# sa612_lm386.net
KiCad netlist of a schematic drawn in EAGLE
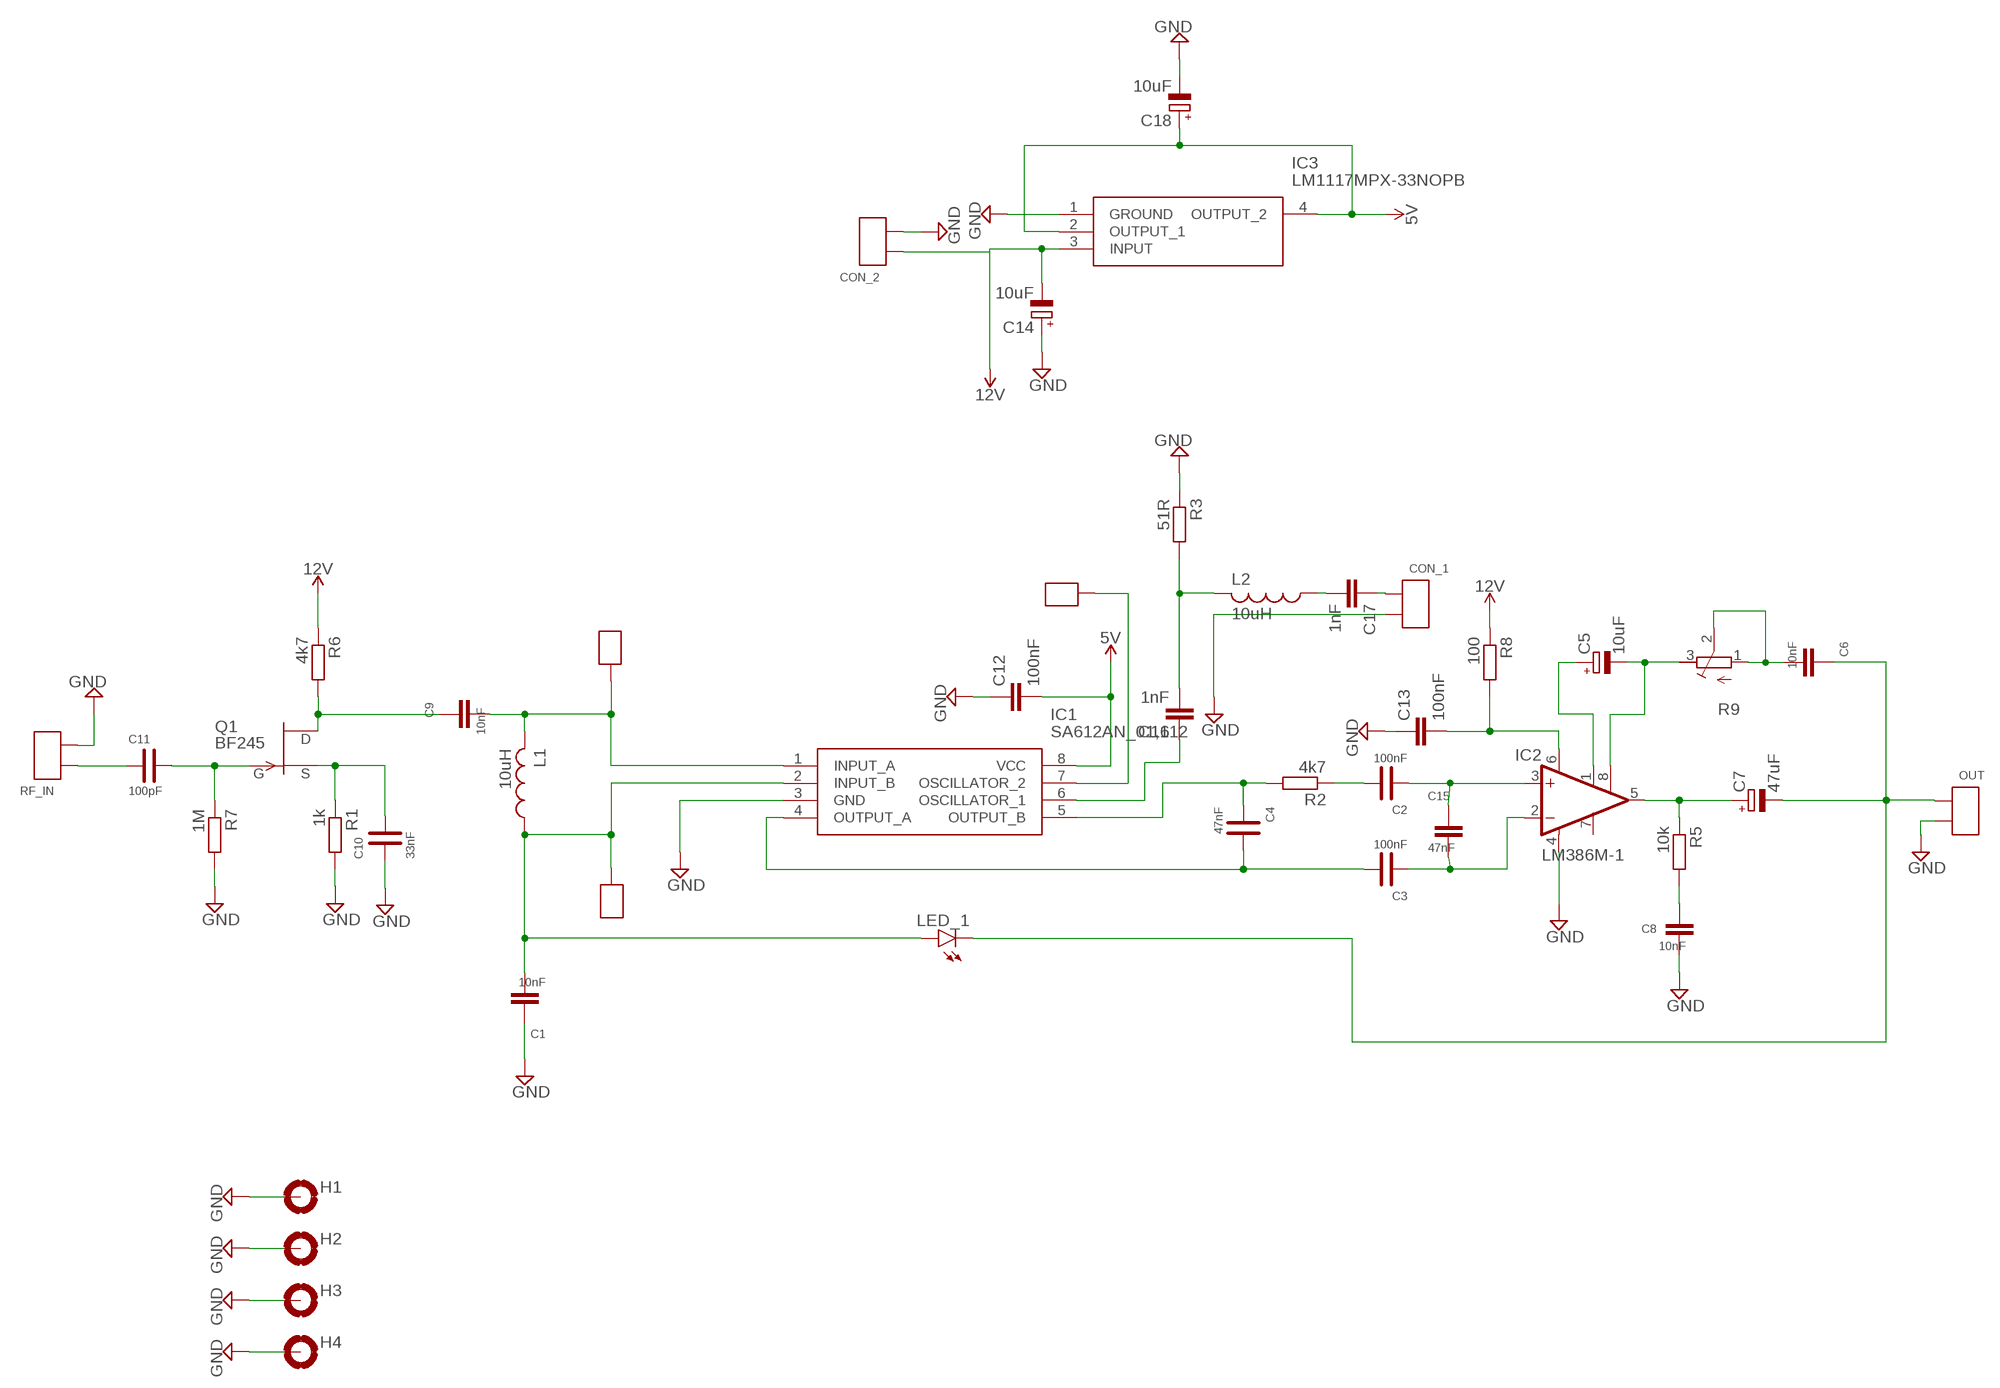
[diagram p0: schematic, sheet 1]

(export (version "E")
  (design (tool "Eeschema 10.0.6"))
  (components
    (comp (ref "C1")
      (value "10nF")
      (footprint "eagle-import:C0805")
      (libsource (lib "eagle-import") (part "C_0805_SMD"))
    )
    (comp (ref "C2")
      (value "100nF")
      (footprint "eagle-import:C0805K")
      (libsource (lib "eagle-import") (part "C_0805_PTH"))
    )
    (comp (ref "C3")
      (value "100nF")
      (footprint "eagle-import:C0805K")
      (libsource (lib "eagle-import") (part "C_0805_PTH"))
    )
    (comp (ref "C4")
      (value "47nF")
      (footprint "eagle-import:C0805K")
      (libsource (lib "eagle-import") (part "C_0805_PTH"))
    )
    (comp (ref "C5")
      (value "10uF")
      (footprint "eagle-import:E5-5")
      (libsource (lib "eagle-import") (part "C_POL"))
    )
    (comp (ref "C6")
      (value "10nF")
      (footprint "eagle-import:C0805")
      (libsource (lib "eagle-import") (part "C_0805_SMD"))
    )
    (comp (ref "C7")
      (value "47uF")
      (footprint "eagle-import:E5-5")
      (libsource (lib "eagle-import") (part "C_POL"))
    )
    (comp (ref "C8")
      (value "10nF")
      (footprint "eagle-import:C0805")
      (libsource (lib "eagle-import") (part "C_0805_SMD"))
    )
    (comp (ref "C9")
      (value "10nF")
      (footprint "eagle-import:C0805")
      (libsource (lib "eagle-import") (part "C_0805_SMD"))
    )
    (comp (ref "C10")
      (value "33nF")
      (footprint "eagle-import:C0805K")
      (libsource (lib "eagle-import") (part "C_0805_PTH"))
    )
    (comp (ref "C11")
      (value "100pF")
      (footprint "eagle-import:C0805K")
      (libsource (lib "eagle-import") (part "C_0805_PTH"))
    )
    (comp (ref "C12")
      (value "100nF")
      (footprint "eagle-import:C0805")
      (libsource (lib "eagle-import") (part "C_0805_SMD"))
    )
    (comp (ref "C13")
      (value "100nF")
      (footprint "eagle-import:C0805")
      (libsource (lib "eagle-import") (part "C_0805_SMD"))
    )
    (comp (ref "C14")
      (value "10uF")
      (footprint "eagle-import:E5-5")
      (libsource (lib "eagle-import") (part "C_POL"))
    )
    (comp (ref "C15")
      (value "47nF")
      (footprint "eagle-import:C0805")
      (libsource (lib "eagle-import") (part "C_0805_SMD"))
    )
    (comp (ref "C16")
      (value "1nF")
      (footprint "eagle-import:C0805")
      (libsource (lib "eagle-import") (part "C_0805_SMD"))
    )
    (comp (ref "C17")
      (value "1nF")
      (footprint "eagle-import:C0805")
      (libsource (lib "eagle-import") (part "C_0805_SMD"))
    )
    (comp (ref "C18")
      (value "10uF")
      (footprint "eagle-import:E5-5")
      (libsource (lib "eagle-import") (part "C_POL"))
    )
    (comp (ref "CON_1")
      (value "2X_SMD_PTH_PIN")
      (footprint "eagle-import:2X_SMD_PTH")
      (libsource (lib "eagle-import") (part "2X_SMD_PTH_PIN"))
    )
    (comp (ref "CON_2")
      (value "2X_SMD_PTH_PIN")
      (footprint "eagle-import:2X_SMD_PTH")
      (libsource (lib "eagle-import") (part "2X_SMD_PTH_PIN"))
    )
    (comp (ref "H1")
      (value "MOUNT-PAD-ROUND3.0")
      (footprint "eagle-import:3,0-PAD")
      (libsource (lib "eagle-import") (part "MOUNT-PAD-ROUND3.0"))
    )
    (comp (ref "H2")
      (value "MOUNT-PAD-ROUND3.0")
      (footprint "eagle-import:3,0-PAD")
      (libsource (lib "eagle-import") (part "MOUNT-PAD-ROUND3.0"))
    )
    (comp (ref "H3")
      (value "MOUNT-PAD-ROUND3.0")
      (footprint "eagle-import:3,0-PAD")
      (libsource (lib "eagle-import") (part "MOUNT-PAD-ROUND3.0"))
    )
    (comp (ref "H4")
      (value "MOUNT-PAD-ROUND3.0")
      (footprint "eagle-import:3,0-PAD")
      (libsource (lib "eagle-import") (part "MOUNT-PAD-ROUND3.0"))
    )
    (comp (ref "IC1")
      (value "SA612AN_01,112")
      (footprint "eagle-import:DIP762W53P254L950H420Q8N")
      (fields
        (field (name "MANUFACTURER_PART_NUMBER") "SA612AN/01,112")
        (field (name "MOUSER_PART_NUMBER") "771-SA612AN/01")
      )
      (libsource (lib "eagle-import") (part "SA612AN_01,112"))
    )
    (comp (ref "IC2")
      (value "LM386M-1")
      (footprint "eagle-import:SO08")
      (libsource (lib "eagle-import") (part "LM386?-M1"))
    )
    (comp (ref "IC3")
      (value "LM1117MPX-33NOPB")
      (footprint "eagle-import:SOT230P700X180-4N")
      (fields (field (name "MOUSER_PART_NUMBER") "863-LM1117MPX-33NOPB"))
      (libsource (lib "eagle-import") (part "LM1117MPX-33NOPB"))
    )
    (comp (ref "IN_A")
      (value "SMD_PIN")
      (footprint "eagle-import:SMD_PIN")
      (libsource (lib "eagle-import") (part "SMD_PIN"))
    )
    (comp (ref "IN_B")
      (value "SMD_PIN")
      (footprint "eagle-import:SMD_PIN")
      (libsource (lib "eagle-import") (part "SMD_PIN"))
    )
    (comp (ref "L1")
      (value "10uH")
      (footprint "eagle-import:M0805")
      (libsource (lib "eagle-import") (part "L_0805_PTH"))
    )
    (comp (ref "L2")
      (value "10uH")
      (footprint "eagle-import:M0805")
      (libsource (lib "eagle-import") (part "L_0805_PTH"))
    )
    (comp (ref "LED_1")
      (value "LED_0805_PTH")
      (footprint "eagle-import:CHIP-LED0805")
      (libsource (lib "eagle-import") (part "LED_0805_PTH"))
    )
    (comp (ref "OUT")
      (value "2X_SMD_PTH_PIN")
      (footprint "eagle-import:2X_SMD_PTH")
      (libsource (lib "eagle-import") (part "2X_SMD_PTH_PIN"))
    )
    (comp (ref "P_1")
      (value "SMD_PIN")
      (footprint "eagle-import:SMD_PIN")
      (libsource (lib "eagle-import") (part "SMD_PIN"))
    )
    (comp (ref "Q1")
      (value "BF245")
      (footprint "eagle-import:TO92")
      (libsource (lib "eagle-import") (part "BF245"))
    )
    (comp (ref "R1")
      (value "1k")
      (footprint "eagle-import:R0805")
      (libsource (lib "eagle-import") (part "R_0805_PTH"))
    )
    (comp (ref "R2")
      (value "4k7")
      (footprint "eagle-import:R0805W")
      (libsource (lib "eagle-import") (part "R_0805_SMD"))
    )
    (comp (ref "R3")
      (value "51R")
      (footprint "eagle-import:R0805W")
      (libsource (lib "eagle-import") (part "R_0805_SMD"))
    )
    (comp (ref "R5")
      (value "10k")
      (footprint "eagle-import:R0805W")
      (libsource (lib "eagle-import") (part "R_0805_SMD"))
    )
    (comp (ref "R6")
      (value "4k7")
      (footprint "eagle-import:R0805")
      (libsource (lib "eagle-import") (part "R_0805_PTH"))
    )
    (comp (ref "R7")
      (value "1M")
      (footprint "eagle-import:R0805")
      (libsource (lib "eagle-import") (part "R_0805_PTH"))
    )
    (comp (ref "R8")
      (value "100")
      (footprint "eagle-import:R0805W")
      (libsource (lib "eagle-import") (part "R_0805_SMD"))
    )
    (comp (ref "R9")
      (value "R-TRIMM64W")
      (footprint "eagle-import:RTRIM64W")
      (libsource (lib "eagle-import") (part "R-TRIMM64W"))
    )
    (comp (ref "RF_IN")
      (value "2X_SMD_PTH_PIN")
      (footprint "eagle-import:2X_SMD_PTH")
      (libsource (lib "eagle-import") (part "2X_SMD_PTH_PIN"))
    )
  )
  (nets
    (net (code "1") (name "5V") (class "Default")
      (node (ref "C12") (pin "2") (pinfunction "2_2") (pintype "passive"))
      (node (ref "C18") (pin "+") (pinfunction "+_+") (pintype "passive"))
      (node (ref "IC1") (pin "8") (pinfunction "VCC_8") (pintype "bidirectional"))
      (node (ref "IC3") (pin "2") (pinfunction "OUTPUT_1_2") (pintype "bidirectional"))
      (node (ref "IC3") (pin "4") (pinfunction "OUTPUT_2_4") (pintype "bidirectional"))
    )
    (net (code "2") (name "12V") (class "Default")
      (node (ref "C14") (pin "-") (pinfunction "-_-") (pintype "passive"))
      (node (ref "CON_2") (pin "P$1") (pinfunction "PIN0_P$1") (pintype "bidirectional"))
      (node (ref "CON_2") (pin "T$1") (pinfunction "PIN0_T$1") (pintype "bidirectional"))
      (node (ref "IC3") (pin "3") (pinfunction "INPUT_3") (pintype "bidirectional"))
      (node (ref "R6") (pin "1") (pinfunction "1_1") (pintype "passive"))
      (node (ref "R6") (pin "P$1") (pinfunction "1_P$1") (pintype "passive"))
      (node (ref "R8") (pin "1") (pinfunction "1_1") (pintype "passive"))
    )
    (net (code "3") (name "GND") (class "Default")
      (node (ref "C1") (pin "1") (pinfunction "1_1") (pintype "passive"))
      (node (ref "C10") (pin "1") (pinfunction "1_1") (pintype "bidirectional"))
      (node (ref "C10") (pin "P$1") (pinfunction "1_P$1") (pintype "bidirectional"))
      (node (ref "C12") (pin "1") (pinfunction "1_1") (pintype "passive"))
      (node (ref "C13") (pin "1") (pinfunction "1_1") (pintype "passive"))
      (node (ref "C14") (pin "+") (pinfunction "+_+") (pintype "passive"))
      (node (ref "C18") (pin "-") (pinfunction "-_-") (pintype "passive"))
      (node (ref "C8") (pin "2") (pinfunction "2_2") (pintype "passive"))
      (node (ref "CON_1") (pin "P$2") (pinfunction "PIN1_P$2") (pintype "bidirectional"))
      (node (ref "CON_1") (pin "T$2") (pinfunction "PIN1_T$2") (pintype "bidirectional"))
      (node (ref "CON_2") (pin "P$2") (pinfunction "PIN1_P$2") (pintype "bidirectional"))
      (node (ref "CON_2") (pin "T$2") (pinfunction "PIN1_T$2") (pintype "bidirectional"))
      (node (ref "H1") (pin "B3,0") (pinfunction "MOUNT_B3,0") (pintype "passive"))
      (node (ref "H2") (pin "B3,0") (pinfunction "MOUNT_B3,0") (pintype "passive"))
      (node (ref "H3") (pin "B3,0") (pinfunction "MOUNT_B3,0") (pintype "passive"))
      (node (ref "H4") (pin "B3,0") (pinfunction "MOUNT_B3,0") (pintype "passive"))
      (node (ref "IC1") (pin "3") (pinfunction "GND_3") (pintype "bidirectional"))
      (node (ref "IC2") (pin "4") (pinfunction "GND_4") (pintype "power_in"))
      (node (ref "IC3") (pin "1") (pinfunction "GROUND_1") (pintype "bidirectional"))
      (node (ref "OUT") (pin "P$2") (pinfunction "PIN1_P$2") (pintype "bidirectional"))
      (node (ref "OUT") (pin "T$2") (pinfunction "PIN1_T$2") (pintype "bidirectional"))
      (node (ref "R1") (pin "2") (pinfunction "2_2") (pintype "passive"))
      (node (ref "R1") (pin "P$2") (pinfunction "2_P$2") (pintype "passive"))
      (node (ref "R3") (pin "1") (pinfunction "1_1") (pintype "passive"))
      (node (ref "R7") (pin "2") (pinfunction "2_2") (pintype "passive"))
      (node (ref "R7") (pin "P$2") (pinfunction "2_P$2") (pintype "passive"))
      (node (ref "RF_IN") (pin "P$2") (pinfunction "PIN1_P$2") (pintype "bidirectional"))
      (node (ref "RF_IN") (pin "T$2") (pinfunction "PIN1_T$2") (pintype "bidirectional"))
    )
    (net (code "4") (name "Net-(C2-2-PadP$2)") (class "Default")
      (node (ref "C2") (pin "2") (pinfunction "2_2") (pintype "bidirectional"))
      (node (ref "C2") (pin "P$2") (pinfunction "2_P$2") (pintype "bidirectional"))
      (node (ref "R2") (pin "1") (pinfunction "1_1") (pintype "passive"))
    )
    (net (code "5") (name "Net-(C5-Pad+)") (class "Default")
      (node (ref "C5") (pin "+") (pinfunction "+_+") (pintype "passive"))
      (node (ref "IC2") (pin "1") (pinfunction "GAIN_1") (pintype "passive"))
    )
    (net (code "6") (name "Net-(C6-Pad1)") (class "Default")
      (node (ref "C6") (pin "1") (pinfunction "1_1") (pintype "passive"))
      (node (ref "C7") (pin "-") (pinfunction "-_-") (pintype "passive"))
      (node (ref "LED_1") (pin "C") (pinfunction "C_C") (pintype "passive"))
      (node (ref "LED_1") (pin "CP") (pinfunction "C_CP") (pintype "passive"))
      (node (ref "OUT") (pin "P$1") (pinfunction "PIN0_P$1") (pintype "bidirectional"))
      (node (ref "OUT") (pin "T$1") (pinfunction "PIN0_T$1") (pintype "bidirectional"))
    )
    (net (code "7") (name "Net-(C8-Pad1)") (class "Default")
      (node (ref "C8") (pin "1") (pinfunction "1_1") (pintype "passive"))
      (node (ref "R5") (pin "2") (pinfunction "2_2") (pintype "passive"))
    )
    (net (code "8") (name "Net-(C11-1-PadP$1)") (class "Default")
      (node (ref "C11") (pin "1") (pinfunction "1_1") (pintype "bidirectional"))
      (node (ref "C11") (pin "P$1") (pinfunction "1_P$1") (pintype "bidirectional"))
      (node (ref "RF_IN") (pin "P$1") (pinfunction "PIN0_P$1") (pintype "bidirectional"))
      (node (ref "RF_IN") (pin "T$1") (pinfunction "PIN0_T$1") (pintype "bidirectional"))
    )
    (net (code "9") (name "Net-(C16-Pad2)") (class "Default")
      (node (ref "C16") (pin "2") (pinfunction "2_2") (pintype "passive"))
      (node (ref "L2") (pin "2") (pinfunction "2_2") (pintype "passive"))
      (node (ref "L2") (pin "P$2") (pinfunction "2_P$2") (pintype "passive"))
      (node (ref "R3") (pin "2") (pinfunction "2_2") (pintype "passive"))
    )
    (net (code "10") (name "Net-(C17-Pad1)") (class "Default")
      (node (ref "C17") (pin "1") (pinfunction "1_1") (pintype "passive"))
      (node (ref "CON_1") (pin "P$1") (pinfunction "PIN0_P$1") (pintype "bidirectional"))
      (node (ref "CON_1") (pin "T$1") (pinfunction "PIN0_T$1") (pintype "bidirectional"))
    )
    (net (code "11") (name "Net-(C17-Pad2)") (class "Default")
      (node (ref "C17") (pin "2") (pinfunction "2_2") (pintype "passive"))
      (node (ref "L2") (pin "1") (pinfunction "1_1") (pintype "passive"))
      (node (ref "L2") (pin "P$1") (pinfunction "1_P$1") (pintype "passive"))
    )
    (net (code "12") (name "Net-(IC1-INPUT_A)") (class "Default")
      (node (ref "C9") (pin "2") (pinfunction "2_2") (pintype "passive"))
      (node (ref "IC1") (pin "1") (pinfunction "INPUT_A_1") (pintype "bidirectional"))
      (node (ref "IN_A") (pin "P$1") (pinfunction "P$1_P$1") (pintype "bidirectional"))
      (node (ref "L1") (pin "2") (pinfunction "2_2") (pintype "passive"))
      (node (ref "L1") (pin "P$2") (pinfunction "2_P$2") (pintype "passive"))
    )
    (net (code "13") (name "Net-(IC1-INPUT_B)") (class "Default")
      (node (ref "C1") (pin "2") (pinfunction "2_2") (pintype "passive"))
      (node (ref "IC1") (pin "2") (pinfunction "INPUT_B_2") (pintype "bidirectional"))
      (node (ref "IN_B") (pin "P$1") (pinfunction "P$1_P$1") (pintype "bidirectional"))
      (node (ref "L1") (pin "1") (pinfunction "1_1") (pintype "passive"))
      (node (ref "L1") (pin "P$1") (pinfunction "1_P$1") (pintype "passive"))
      (node (ref "LED_1") (pin "A") (pinfunction "A_A") (pintype "passive"))
      (node (ref "LED_1") (pin "AP") (pinfunction "A_AP") (pintype "passive"))
    )
    (net (code "14") (name "Net-(IC1-OSCILLATOR_1)") (class "Default")
      (node (ref "C16") (pin "1") (pinfunction "1_1") (pintype "passive"))
      (node (ref "IC1") (pin "6") (pinfunction "OSCILLATOR_1_6") (pintype "bidirectional"))
    )
    (net (code "15") (name "Net-(IC1-OSCILLATOR_2)") (class "Default")
      (node (ref "IC1") (pin "7") (pinfunction "OSCILLATOR_2_7") (pintype "bidirectional"))
      (node (ref "P_1") (pin "P$1") (pinfunction "P$1_P$1") (pintype "bidirectional"))
    )
    (net (code "16") (name "Net-(IC1-OUTPUT_A)") (class "Default")
      (node (ref "C3") (pin "2") (pinfunction "2_2") (pintype "bidirectional"))
      (node (ref "C3") (pin "P$2") (pinfunction "2_P$2") (pintype "bidirectional"))
      (node (ref "C4") (pin "2") (pinfunction "2_2") (pintype "bidirectional"))
      (node (ref "C4") (pin "P$2") (pinfunction "2_P$2") (pintype "bidirectional"))
      (node (ref "IC1") (pin "4") (pinfunction "OUTPUT_A_4") (pintype "bidirectional"))
    )
    (net (code "17") (name "Net-(IC1-OUTPUT_B)") (class "Default")
      (node (ref "C4") (pin "1") (pinfunction "1_1") (pintype "bidirectional"))
      (node (ref "C4") (pin "P$1") (pinfunction "1_P$1") (pintype "bidirectional"))
      (node (ref "IC1") (pin "5") (pinfunction "OUTPUT_B_5") (pintype "bidirectional"))
      (node (ref "R2") (pin "2") (pinfunction "2_2") (pintype "passive"))
    )
    (net (code "18") (name "Net-(IC2-+IN)") (class "Default")
      (node (ref "C15") (pin "1") (pinfunction "1_1") (pintype "passive"))
      (node (ref "C2") (pin "1") (pinfunction "1_1") (pintype "bidirectional"))
      (node (ref "C2") (pin "P$1") (pinfunction "1_P$1") (pintype "bidirectional"))
      (node (ref "IC2") (pin "3") (pinfunction "+IN_3") (pintype "input"))
    )
    (net (code "19") (name "Net-(IC2--IN)") (class "Default")
      (node (ref "C15") (pin "2") (pinfunction "2_2") (pintype "passive"))
      (node (ref "C3") (pin "1") (pinfunction "1_1") (pintype "bidirectional"))
      (node (ref "C3") (pin "P$1") (pinfunction "1_P$1") (pintype "bidirectional"))
      (node (ref "IC2") (pin "2") (pinfunction "-IN_2") (pintype "input"))
    )
    (net (code "20") (name "Net-(IC2-OUT)") (class "Default")
      (node (ref "C7") (pin "+") (pinfunction "+_+") (pintype "passive"))
      (node (ref "IC2") (pin "5") (pinfunction "OUT_5") (pintype "output"))
      (node (ref "R5") (pin "1") (pinfunction "1_1") (pintype "passive"))
    )
    (net (code "21") (name "Net-(IC2-VS)") (class "Default")
      (node (ref "C13") (pin "2") (pinfunction "2_2") (pintype "passive"))
      (node (ref "IC2") (pin "6") (pinfunction "VS_6") (pintype "power_in"))
      (node (ref "R8") (pin "2") (pinfunction "2_2") (pintype "passive"))
    )
    (net (code "22") (name "Net-(Q1-D)") (class "Default")
      (node (ref "C9") (pin "1") (pinfunction "1_1") (pintype "passive"))
      (node (ref "Q1") (pin "1") (pinfunction "D_1") (pintype "passive"))
      (node (ref "R6") (pin "2") (pinfunction "2_2") (pintype "passive"))
      (node (ref "R6") (pin "P$2") (pinfunction "2_P$2") (pintype "passive"))
    )
    (net (code "23") (name "Net-(Q1-G)") (class "Default")
      (node (ref "C11") (pin "2") (pinfunction "2_2") (pintype "bidirectional"))
      (node (ref "C11") (pin "P$2") (pinfunction "2_P$2") (pintype "bidirectional"))
      (node (ref "Q1") (pin "3") (pinfunction "G_3") (pintype "passive"))
      (node (ref "R7") (pin "1") (pinfunction "1_1") (pintype "passive"))
      (node (ref "R7") (pin "P$1") (pinfunction "1_P$1") (pintype "passive"))
    )
    (net (code "24") (name "Net-(Q1-S)") (class "Default")
      (node (ref "C10") (pin "2") (pinfunction "2_2") (pintype "bidirectional"))
      (node (ref "C10") (pin "P$2") (pinfunction "2_P$2") (pintype "bidirectional"))
      (node (ref "Q1") (pin "2") (pinfunction "S_2") (pintype "passive"))
      (node (ref "R1") (pin "1") (pinfunction "1_1") (pintype "passive"))
      (node (ref "R1") (pin "P$1") (pinfunction "1_P$1") (pintype "passive"))
    )
    (net (code "25") (name "Net-(R9-A)") (class "Default")
      (node (ref "C6") (pin "2") (pinfunction "2_2") (pintype "passive"))
      (node (ref "R9") (pin "1") (pinfunction "A_1") (pintype "passive"))
      (node (ref "R9") (pin "2") (pinfunction "S_2") (pintype "passive"))
    )
    (net (code "26") (name "Net-(R9-E)") (class "Default")
      (node (ref "C5") (pin "-") (pinfunction "-_-") (pintype "passive"))
      (node (ref "IC2") (pin "8") (pinfunction "GAIN_8") (pintype "passive"))
      (node (ref "R9") (pin "3") (pinfunction "E_3") (pintype "passive"))
    )
    (net (code "27") (name "unconnected-(IC2-BYPASS-Pad7)") (class "Default")
      (node (ref "IC2") (pin "7") (pinfunction "BYPASS_7") (pintype "passive"))
    )
  )
)
